# SCH_uCurrent_2024-10-28.net
KiCad netlist of a schematic drawn in EasyEDA
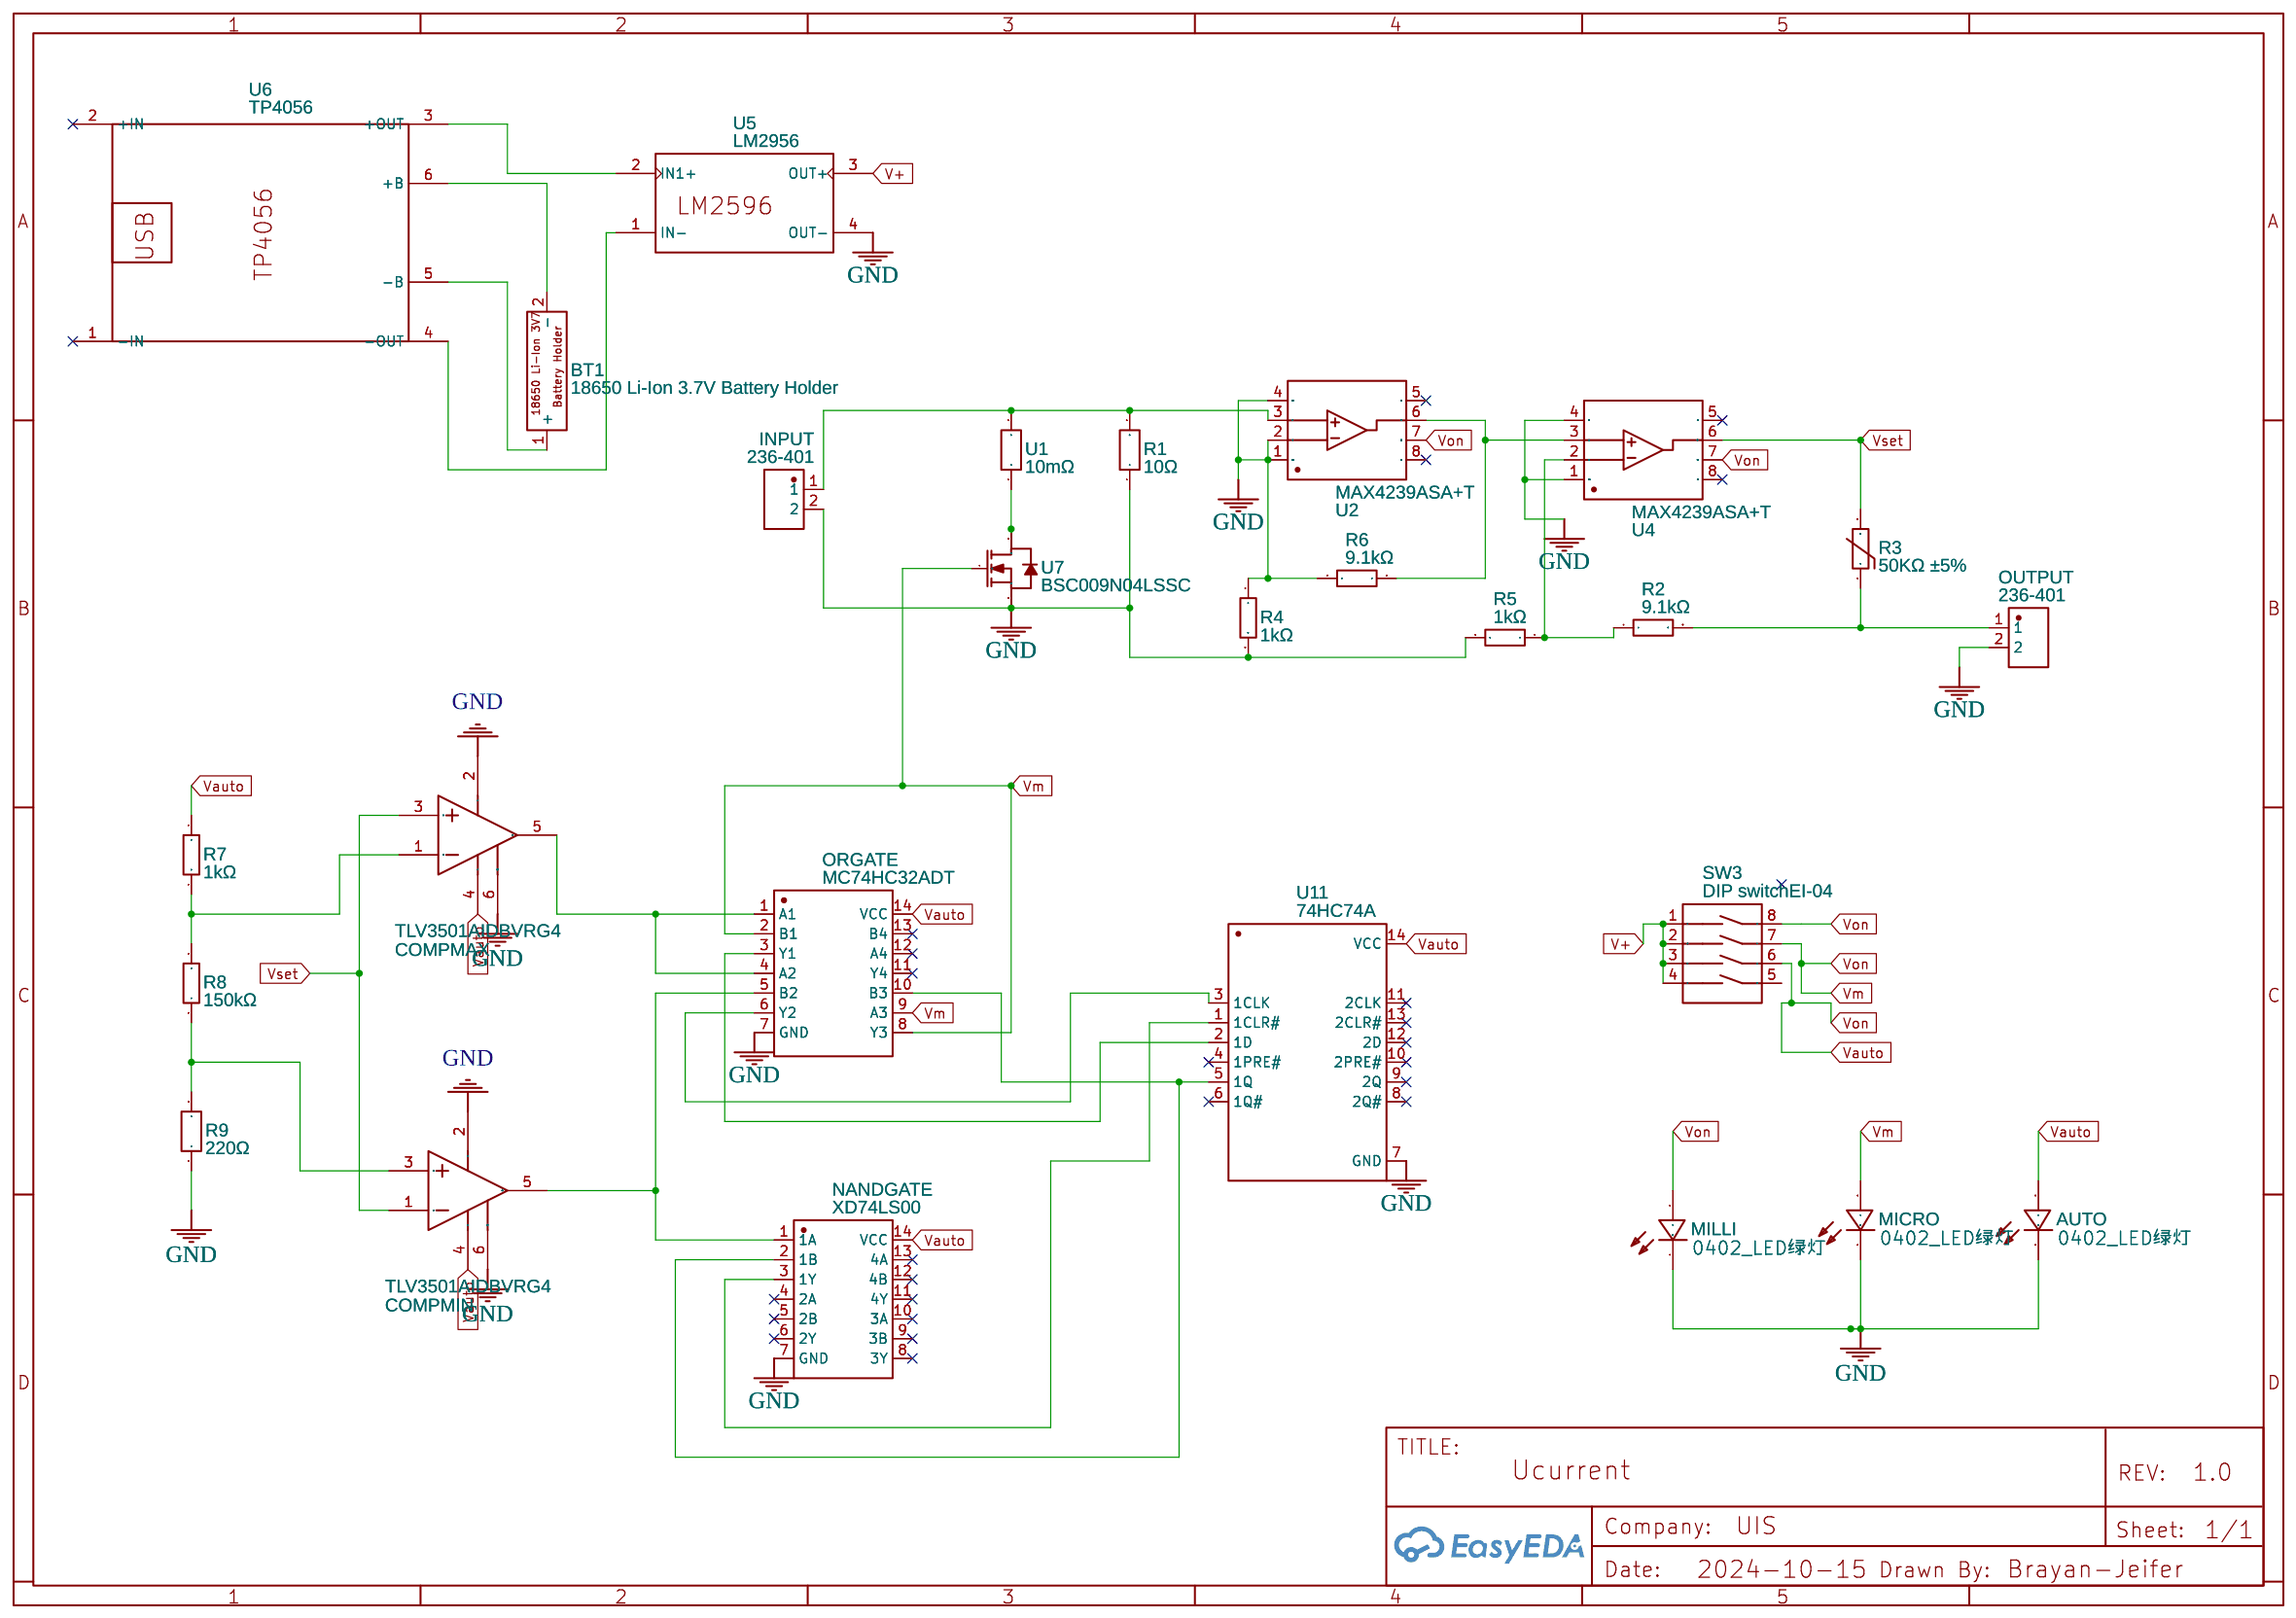
[diagram p0: schematic sheet]

(export (version "E")
  (design (tool "Eeschema 10.0.6"))
  (components
    (comp (ref "AUTO") (value "0402_LED绿灯") (libsource (lib "") (part "0402_LED绿灯_2")))
    (comp (ref "BT1")
      (value "18650 Li-Ion 3.7V Battery Holder")
      (fields (field (name "Manufacturer Part") "18650_Li_BT_3P7V") (field (name "Manufacturer") "Smartcube"))
      (libsource (lib "") (part "18650 Li-Ion 3.7V Battery Holder"))
    )
    (comp (ref "COMPMAX")
      (value "TLV3501AIDBVRG4")
      (fields (field (name "Manufacturer") "TI(德州仪器)"))
      (libsource (lib "") (part "TLV3501AIDBVRG4_1"))
    )
    (comp (ref "COMPMIN")
      (value "TLV3501AIDBVRG4")
      (fields (field (name "Manufacturer") "TI(德州仪器)"))
      (libsource (lib "") (part "TLV3501AIDBVRG4"))
    )
    (comp (ref "INPUT")
      (value "236-401")
      (fields (field (name "Manufacturer") "WAGO(万可)"))
      (libsource (lib "") (part "236-401"))
    )
    (comp (ref "MICRO") (value "0402_LED绿灯") (libsource (lib "") (part "0402_LED绿灯")))
    (comp (ref "MILLI") (value "0402_LED绿灯") (libsource (lib "") (part "0402_LED绿灯_1")))
    (comp (ref "NANDGATE")
      (value "XD74LS00")
      (fields (field (name "Manufacturer") "XINLUDA(信路达)"))
      (libsource (lib "") (part "XD74LS00"))
    )
    (comp (ref "ORGATE")
      (value "MC74HC32ADT")
      (fields (field (name "Manufacturer") "onsemi(安森美)"))
      (libsource (lib "") (part "MC74HC32ADT"))
    )
    (comp (ref "OUTPUT")
      (value "236-401")
      (fields (field (name "Manufacturer") "WAGO(万可)"))
      (libsource (lib "") (part "236-401_1"))
    )
    (comp (ref "R1")
      (value "10Ω")
      (fields
        (field (name "Manufacturer Part") "CRCW080510R0FKEA")
        (field (name "Manufacturer") "VISHAY(威世)")
      )
      (libsource (lib "") (part "CRCW080510R0FKEA"))
    )
    (comp (ref "R2")
      (value "9.1kΩ")
      (fields (field (name "Manufacturer Part") "RC1206JR-079K1L") (field (name "Manufacturer") "YAGEO(国巨)"))
      (libsource (lib "") (part "RC1206JR-079K1L"))
    )
    (comp (ref "R3")
      (value "50KΩ ±5%")
      (fields (field (name "Manufacturer Part") "MF52A503J3950 (A1)") (field (name "Manufacturer") "时恒"))
      (libsource (lib "") (part "50KΩ ±5%"))
    )
    (comp (ref "R4")
      (value "1kΩ")
      (fields (field (name "Manufacturer Part") "CR-06FL7----1K") (field (name "Manufacturer") "Viking(光颉)"))
      (libsource (lib "") (part "CR-06FL7----1K"))
    )
    (comp (ref "R5")
      (value "1kΩ")
      (fields (field (name "Manufacturer Part") "CR-06FL7----1K") (field (name "Manufacturer") "Viking(光颉)"))
      (libsource (lib "") (part "CR-06FL7----1K_1"))
    )
    (comp (ref "R6")
      (value "9.1kΩ")
      (fields (field (name "Manufacturer Part") "RC1206JR-079K1L") (field (name "Manufacturer") "YAGEO(国巨)"))
      (libsource (lib "") (part "RC1206JR-079K1L"))
    )
    (comp (ref "R7")
      (value "1kΩ")
      (fields (field (name "Manufacturer Part") "CR-06FL7----1K") (field (name "Manufacturer") "Viking(光颉)"))
      (libsource (lib "") (part "CR-06FL7----1K"))
    )
    (comp (ref "R8")
      (value "150kΩ")
      (fields
        (field (name "Manufacturer Part") "0201WMF1503TCE")
        (field (name "Manufacturer") "UNI-ROYAL(厚声)")
      )
      (libsource (lib "") (part "0201WMF1503TCE"))
    )
    (comp (ref "R9")
      (value "220Ω")
      (fields
        (field (name "Manufacturer Part") "0805W8D2200T5E")
        (field (name "Manufacturer") "UNI-ROYAL(厚声)")
      )
      (libsource (lib "") (part "0805W8D2200T5E"))
    )
    (comp (ref "SW3")
      (value "DIP switchEI-04")
      (fields (field (name "Manufacturer Part") "拨码开关EI-04") (field (name "Manufacturer") "圜达"))
      (libsource (lib "") (part "DIP switchEI-04"))
    )
    (comp (ref "U1")
      (value "10mΩ")
      (fields (field (name "Manufacturer Part") "WSL2512R0100FEA") (field (name "Manufacturer") "VISHAY(威世)"))
      (libsource (lib "") (part "WSL2512R0100FEA"))
    )
    (comp (ref "U2")
      (value "MAX4239ASA+T")
      (fields (field (name "Manufacturer") "ADI(亚德诺)/MAXIM(美信)"))
      (libsource (lib "") (part "MAX4239ASA+T"))
    )
    (comp (ref "U4")
      (value "MAX4239ASA+T")
      (fields (field (name "Manufacturer") "ADI(亚德诺)/MAXIM(美信)"))
      (libsource (lib "") (part "MAX4239ASA+T"))
    )
    (comp (ref "U5") (value "LM2956") (libsource (lib "") (part "LM2956")))
    (comp (ref "U6")
      (value "TP4056")
      (fields (field (name "Manufacturer") "Handsontec"))
      (libsource (lib "") (part "TP4056"))
    )
    (comp (ref "U7") (value "BSC009N04LSSC") (libsource (lib "") (part "BSC009N04LSSC")))
    (comp (ref "U11")
      (value "74HC74A")
      (fields (field (name "Manufacturer") "onsemi(安森美)"))
      (libsource (lib "") (part "74HC74A"))
    )
  )
  (nets
    (net (code "1") (name "GND") (class "Default")
      (node (ref "AUTO") (pin "1") (pinfunction "C_1") (pintype "unspecified"))
      (node (ref "COMPMAX") (pin "2") (pinfunction "V-_2") (pintype "passive"))
      (node (ref "COMPMAX") (pin "6") (pinfunction "SHDN_6") (pintype "unspecified"))
      (node (ref "COMPMIN") (pin "2") (pinfunction "V-_2") (pintype "passive"))
      (node (ref "COMPMIN") (pin "6") (pinfunction "SHDN_6") (pintype "unspecified"))
      (node (ref "INPUT") (pin "2") (pinfunction "2_2") (pintype "unspecified"))
      (node (ref "MICRO") (pin "1") (pinfunction "C_1") (pintype "unspecified"))
      (node (ref "MILLI") (pin "1") (pinfunction "C_1") (pintype "unspecified"))
      (node (ref "NANDGATE") (pin "7") (pinfunction "GND_7") (pintype "unspecified"))
      (node (ref "ORGATE") (pin "7") (pinfunction "GND_7") (pintype "unspecified"))
      (node (ref "OUTPUT") (pin "2") (pinfunction "2_2") (pintype "unspecified"))
      (node (ref "R1") (pin "1") (pinfunction "1_1") (pintype "unspecified"))
      (node (ref "R4") (pin "1") (pinfunction "1_1") (pintype "unspecified"))
      (node (ref "R4") (pin "2") (pinfunction "2_2") (pintype "unspecified"))
      (node (ref "R5") (pin "2") (pinfunction "2_2") (pintype "unspecified"))
      (node (ref "R6") (pin "1") (pinfunction "1_1") (pintype "unspecified"))
      (node (ref "R9") (pin "1") (pinfunction "1_1") (pintype "unspecified"))
      (node (ref "U11") (pin "7") (pinfunction "GND_7") (pintype "unspecified"))
      (node (ref "U2") (pin "1") (pinfunction "SHDN#_1") (pintype "unspecified"))
      (node (ref "U2") (pin "2") (pinfunction "IN-_2") (pintype "unspecified"))
      (node (ref "U2") (pin "4") (pinfunction "GND_4") (pintype "unspecified"))
      (node (ref "U4") (pin "1") (pinfunction "SHDN#_1") (pintype "unspecified"))
      (node (ref "U4") (pin "4") (pinfunction "GND_4") (pintype "unspecified"))
      (node (ref "U5") (pin "4") (pinfunction "OUT-_4") (pintype "unspecified"))
      (node (ref "U7") (pin "1") (pinfunction "S_1") (pintype "unspecified"))
      (node (ref "U7") (pin "2") (pinfunction "S_2") (pintype "unspecified"))
      (node (ref "U7") (pin "3") (pinfunction "S_3") (pintype "unspecified"))
    )
    (net (code "2") (name "Net-(BT1-+)") (class "Default")
      (node (ref "BT1") (pin "1") (pinfunction "+_1") (pintype "passive"))
      (node (ref "U6") (pin "5") (pinfunction "-B_5") (pintype "unspecified"))
    )
    (net (code "3") (name "Net-(BT1--)") (class "Default")
      (node (ref "BT1") (pin "2") (pinfunction "-_2") (pintype "passive"))
      (node (ref "U6") (pin "6") (pinfunction "+B_6") (pintype "unspecified"))
    )
    (net (code "4") (name "Net-(COMPMAX--IN)") (class "Default")
      (node (ref "COMPMAX") (pin "1") (pinfunction "-IN_1") (pintype "unspecified"))
      (node (ref "R7") (pin "2") (pinfunction "2_2") (pintype "unspecified"))
      (node (ref "R8") (pin "2") (pinfunction "2_2") (pintype "unspecified"))
    )
    (net (code "5") (name "Net-(COMPMAX-OUT)") (class "Default")
      (node (ref "COMPMAX") (pin "5") (pinfunction "OUT_5") (pintype "output"))
      (node (ref "ORGATE") (pin "1") (pinfunction "A1_1") (pintype "unspecified"))
      (node (ref "ORGATE") (pin "4") (pinfunction "A2_4") (pintype "unspecified"))
    )
    (net (code "6") (name "Net-(COMPMIN-+IN)") (class "Default")
      (node (ref "COMPMIN") (pin "3") (pinfunction "+IN_3") (pintype "unspecified"))
      (node (ref "R8") (pin "1") (pinfunction "1_1") (pintype "unspecified"))
      (node (ref "R9") (pin "2") (pinfunction "2_2") (pintype "unspecified"))
    )
    (net (code "7") (name "Net-(COMPMIN-OUT)") (class "Default")
      (node (ref "COMPMIN") (pin "5") (pinfunction "OUT_5") (pintype "output"))
      (node (ref "NANDGATE") (pin "1") (pinfunction "1A_1") (pintype "unspecified"))
      (node (ref "ORGATE") (pin "5") (pinfunction "B2_5") (pintype "unspecified"))
    )
    (net (code "8") (name "Net-(NANDGATE-1B)") (class "Default")
      (node (ref "NANDGATE") (pin "2") (pinfunction "1B_2") (pintype "unspecified"))
      (node (ref "ORGATE") (pin "10") (pinfunction "B3_10") (pintype "unspecified"))
      (node (ref "U11") (pin "5") (pinfunction "1Q_5") (pintype "unspecified"))
    )
    (net (code "9") (name "Net-(NANDGATE-1Y)") (class "Default")
      (node (ref "NANDGATE") (pin "3") (pinfunction "1Y_3") (pintype "unspecified"))
      (node (ref "U11") (pin "1") (pinfunction "1CLR#_1") (pintype "unspecified"))
    )
    (net (code "10") (name "Net-(ORGATE-Y1)") (class "Default")
      (node (ref "ORGATE") (pin "3") (pinfunction "Y1_3") (pintype "unspecified"))
      (node (ref "U11") (pin "2") (pinfunction "1D_2") (pintype "unspecified"))
    )
    (net (code "11") (name "Net-(ORGATE-Y2)") (class "Default")
      (node (ref "ORGATE") (pin "6") (pinfunction "Y2_6") (pintype "unspecified"))
      (node (ref "U11") (pin "3") (pinfunction "1CLK_3") (pintype "unspecified"))
    )
    (net (code "12") (name "Net-(OUTPUT-Pad1)") (class "Default")
      (node (ref "OUTPUT") (pin "1") (pinfunction "1_1") (pintype "unspecified"))
      (node (ref "R2") (pin "2") (pinfunction "2_2") (pintype "unspecified"))
      (node (ref "R3") (pin "1") (pinfunction "1_1") (pintype "unspecified"))
    )
    (net (code "13") (name "Net-(U1-Pad1)") (class "Default")
      (node (ref "U1") (pin "1") (pinfunction "1_1") (pintype "unspecified"))
      (node (ref "U7") (pin "5") (pinfunction "D_5") (pintype "unspecified"))
      (node (ref "U7") (pin "6") (pinfunction "D_6") (pintype "unspecified"))
      (node (ref "U7") (pin "7") (pinfunction "D_7") (pintype "unspecified"))
      (node (ref "U7") (pin "8") (pinfunction "D_8") (pintype "unspecified"))
    )
    (net (code "14") (name "Net-(U2-IN+)") (class "Default")
      (node (ref "INPUT") (pin "1") (pinfunction "1_1") (pintype "unspecified"))
      (node (ref "R1") (pin "2") (pinfunction "2_2") (pintype "unspecified"))
      (node (ref "U1") (pin "2") (pinfunction "2_2") (pintype "unspecified"))
      (node (ref "U2") (pin "3") (pinfunction "IN+_3") (pintype "unspecified"))
    )
    (net (code "15") (name "Net-(U2-OUT)") (class "Default")
      (node (ref "R6") (pin "2") (pinfunction "2_2") (pintype "unspecified"))
      (node (ref "U2") (pin "6") (pinfunction "OUT_6") (pintype "unspecified"))
      (node (ref "U4") (pin "3") (pinfunction "IN+_3") (pintype "unspecified"))
    )
    (net (code "16") (name "Net-(U4-IN-)") (class "Default")
      (node (ref "R2") (pin "1") (pinfunction "1_1") (pintype "unspecified"))
      (node (ref "R5") (pin "1") (pinfunction "1_1") (pintype "unspecified"))
      (node (ref "U4") (pin "2") (pinfunction "IN-_2") (pintype "unspecified"))
    )
    (net (code "17") (name "Net-(U5-IN-)") (class "Default")
      (node (ref "U5") (pin "1") (pinfunction "IN-_1") (pintype "unspecified"))
      (node (ref "U6") (pin "4") (pinfunction "-OUT_4") (pintype "unspecified"))
    )
    (net (code "18") (name "Net-(U5-IN1+)") (class "Default")
      (node (ref "U5") (pin "2") (pinfunction "IN1+_2") (pintype "unspecified"))
      (node (ref "U6") (pin "3") (pinfunction "+OUT_3") (pintype "unspecified"))
    )
    (net (code "19") (name "V+") (class "Default")
      (node (ref "SW3") (pin "1") (pinfunction "1_1") (pintype "unspecified"))
      (node (ref "SW3") (pin "2") (pinfunction "2_2") (pintype "unspecified"))
      (node (ref "SW3") (pin "3") (pinfunction "3_3") (pintype "unspecified"))
      (node (ref "SW3") (pin "4") (pinfunction "4_4") (pintype "unspecified"))
      (node (ref "U5") (pin "3") (pinfunction "OUT+_3") (pintype "unspecified"))
    )
    (net (code "20") (name "Vauto") (class "Default")
      (node (ref "AUTO") (pin "2") (pinfunction "A_2") (pintype "unspecified"))
      (node (ref "COMPMAX") (pin "4") (pinfunction "V+_4") (pintype "passive"))
      (node (ref "COMPMIN") (pin "4") (pinfunction "V+_4") (pintype "passive"))
      (node (ref "MICRO") (pin "2") (pinfunction "A_2") (pintype "unspecified"))
      (node (ref "MILLI") (pin "2") (pinfunction "A_2") (pintype "unspecified"))
      (node (ref "NANDGATE") (pin "14") (pinfunction "VCC_14") (pintype "unspecified"))
      (node (ref "ORGATE") (pin "14") (pinfunction "VCC_14") (pintype "unspecified"))
      (node (ref "ORGATE") (pin "2") (pinfunction "B1_2") (pintype "unspecified"))
      (node (ref "ORGATE") (pin "8") (pinfunction "Y3_8") (pintype "unspecified"))
      (node (ref "ORGATE") (pin "9") (pinfunction "A3_9") (pintype "unspecified"))
      (node (ref "R7") (pin "1") (pinfunction "1_1") (pintype "unspecified"))
      (node (ref "SW3") (pin "6") (pinfunction "6_6") (pintype "unspecified"))
      (node (ref "SW3") (pin "7") (pinfunction "7_7") (pintype "unspecified"))
      (node (ref "SW3") (pin "8") (pinfunction "8_8") (pintype "unspecified"))
      (node (ref "U11") (pin "14") (pinfunction "VCC_14") (pintype "unspecified"))
      (node (ref "U2") (pin "7") (pinfunction "VCC_7") (pintype "unspecified"))
      (node (ref "U4") (pin "7") (pinfunction "VCC_7") (pintype "unspecified"))
      (node (ref "U7") (pin "4") (pinfunction "G_4") (pintype "unspecified"))
    )
    (net (code "21") (name "Vset") (class "Default")
      (node (ref "COMPMAX") (pin "3") (pinfunction "+IN_3") (pintype "unspecified"))
      (node (ref "COMPMIN") (pin "1") (pinfunction "-IN_1") (pintype "unspecified"))
      (node (ref "R3") (pin "2") (pinfunction "2_2") (pintype "unspecified"))
      (node (ref "U4") (pin "6") (pinfunction "OUT_6") (pintype "unspecified"))
    )
    (net (code "22") (name "unconnected-(NANDGATE-2A-Pad4)") (class "Default")
      (node (ref "NANDGATE") (pin "4") (pinfunction "2A_4") (pintype "unspecified+no_connect"))
    )
    (net (code "23") (name "unconnected-(NANDGATE-2B-Pad5)") (class "Default")
      (node (ref "NANDGATE") (pin "5") (pinfunction "2B_5") (pintype "unspecified+no_connect"))
    )
    (net (code "24") (name "unconnected-(NANDGATE-2Y-Pad6)") (class "Default")
      (node (ref "NANDGATE") (pin "6") (pinfunction "2Y_6") (pintype "unspecified+no_connect"))
    )
    (net (code "25") (name "unconnected-(NANDGATE-3A-Pad10)") (class "Default")
      (node (ref "NANDGATE") (pin "10") (pinfunction "3A_10") (pintype "unspecified+no_connect"))
    )
    (net (code "26") (name "unconnected-(NANDGATE-3B-Pad9)") (class "Default")
      (node (ref "NANDGATE") (pin "9") (pinfunction "3B_9") (pintype "unspecified+no_connect"))
    )
    (net (code "27") (name "unconnected-(NANDGATE-3Y-Pad8)") (class "Default")
      (node (ref "NANDGATE") (pin "8") (pinfunction "3Y_8") (pintype "unspecified+no_connect"))
    )
    (net (code "28") (name "unconnected-(NANDGATE-4A-Pad13)") (class "Default")
      (node (ref "NANDGATE") (pin "13") (pinfunction "4A_13") (pintype "unspecified+no_connect"))
    )
    (net (code "29") (name "unconnected-(NANDGATE-4B-Pad12)") (class "Default")
      (node (ref "NANDGATE") (pin "12") (pinfunction "4B_12") (pintype "unspecified+no_connect"))
    )
    (net (code "30") (name "unconnected-(NANDGATE-4Y-Pad11)") (class "Default")
      (node (ref "NANDGATE") (pin "11") (pinfunction "4Y_11") (pintype "unspecified+no_connect"))
    )
    (net (code "31") (name "unconnected-(ORGATE-A4-Pad12)") (class "Default")
      (node (ref "ORGATE") (pin "12") (pinfunction "A4_12") (pintype "unspecified+no_connect"))
    )
    (net (code "32") (name "unconnected-(ORGATE-B4-Pad13)") (class "Default")
      (node (ref "ORGATE") (pin "13") (pinfunction "B4_13") (pintype "unspecified+no_connect"))
    )
    (net (code "33") (name "unconnected-(ORGATE-Y4-Pad11)") (class "Default")
      (node (ref "ORGATE") (pin "11") (pinfunction "Y4_11") (pintype "unspecified+no_connect"))
    )
    (net (code "34") (name "unconnected-(SW3-Pad5)") (class "Default")
      (node (ref "SW3") (pin "5") (pinfunction "5_5") (pintype "unspecified"))
    )
    (net (code "35") (name "unconnected-(U2-NC-Pad5)") (class "Default")
      (node (ref "U2") (pin "5") (pinfunction "NC_5") (pintype "unspecified+no_connect"))
    )
    (net (code "36") (name "unconnected-(U2-NC-Pad8)") (class "Default")
      (node (ref "U2") (pin "8") (pinfunction "NC_8") (pintype "unspecified+no_connect"))
    )
    (net (code "37") (name "unconnected-(U4-NC-Pad5)") (class "Default")
      (node (ref "U4") (pin "5") (pinfunction "NC_5") (pintype "unspecified+no_connect"))
    )
    (net (code "38") (name "unconnected-(U4-NC-Pad8)") (class "Default")
      (node (ref "U4") (pin "8") (pinfunction "NC_8") (pintype "unspecified+no_connect"))
    )
    (net (code "39") (name "unconnected-(U6-+IN-Pad2)") (class "Default")
      (node (ref "U6") (pin "2") (pinfunction "+IN_2") (pintype "unspecified+no_connect"))
    )
    (net (code "40") (name "unconnected-(U6--IN-Pad1)") (class "Default")
      (node (ref "U6") (pin "1") (pinfunction "-IN_1") (pintype "unspecified+no_connect"))
    )
    (net (code "41") (name "unconnected-(U11-1PRE#-Pad4)") (class "Default")
      (node (ref "U11") (pin "4") (pinfunction "1PRE#_4") (pintype "unspecified+no_connect"))
    )
    (net (code "42") (name "unconnected-(U11-1Q#-Pad6)") (class "Default")
      (node (ref "U11") (pin "6") (pinfunction "1Q#_6") (pintype "unspecified+no_connect"))
    )
    (net (code "43") (name "unconnected-(U11-2CLK-Pad11)") (class "Default")
      (node (ref "U11") (pin "11") (pinfunction "2CLK_11") (pintype "unspecified+no_connect"))
    )
    (net (code "44") (name "unconnected-(U11-2CLR#-Pad13)") (class "Default")
      (node (ref "U11") (pin "13") (pinfunction "2CLR#_13") (pintype "unspecified+no_connect"))
    )
    (net (code "45") (name "unconnected-(U11-2D-Pad12)") (class "Default")
      (node (ref "U11") (pin "12") (pinfunction "2D_12") (pintype "unspecified+no_connect"))
    )
    (net (code "46") (name "unconnected-(U11-2PRE#-Pad10)") (class "Default")
      (node (ref "U11") (pin "10") (pinfunction "2PRE#_10") (pintype "unspecified+no_connect"))
    )
    (net (code "47") (name "unconnected-(U11-2Q#-Pad8)") (class "Default")
      (node (ref "U11") (pin "8") (pinfunction "2Q#_8") (pintype "unspecified+no_connect"))
    )
    (net (code "48") (name "unconnected-(U11-2Q-Pad9)") (class "Default")
      (node (ref "U11") (pin "9") (pinfunction "2Q_9") (pintype "unspecified+no_connect"))
    )
  )
)
